# PWR_LTM4644.net
KiCad netlist of a schematic drawn in Altium Designer
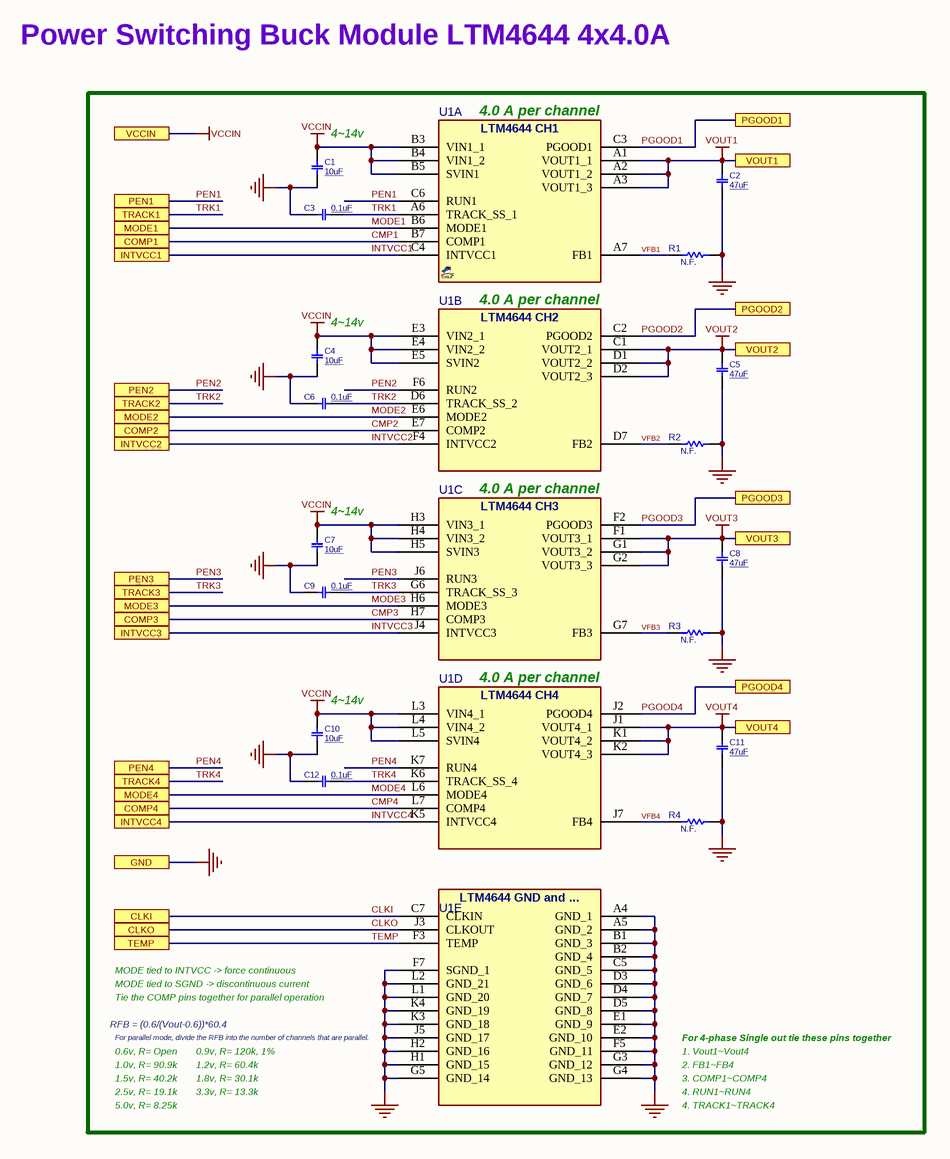
[diagram p0: PWR_LTM4644.SchDoc]

(export (version "E")
  (design (tool "Eeschema 10.0.6"))
  (components
    (comp (ref "C1")
      (value "10uF")
      (footprint "C0805")
      (description "CAP, MLCC")
      (libsource (lib "passive_smd") (part "CAP_SMD_MLCC"))
    )
    (comp (ref "C2")
      (value "47uF")
      (footprint "C0805")
      (description "CAP, MLCC")
      (libsource (lib "passive_smd") (part "CAP_SMD_MLCC"))
    )
    (comp (ref "C3")
      (value "0.1uF")
      (footprint "C0402")
      (description "CAP, MLCC")
      (libsource (lib "passive_smd") (part "CAP_SMD_MLCC"))
    )
    (comp (ref "C4")
      (value "10uF")
      (footprint "C0805")
      (description "CAP, MLCC")
      (libsource (lib "passive_smd") (part "CAP_SMD_MLCC"))
    )
    (comp (ref "C5")
      (value "47uF")
      (footprint "C0805")
      (description "CAP, MLCC")
      (libsource (lib "passive_smd") (part "CAP_SMD_MLCC"))
    )
    (comp (ref "C6")
      (value "0.1uF")
      (footprint "C0402")
      (description "CAP, MLCC")
      (libsource (lib "passive_smd") (part "CAP_SMD_MLCC"))
    )
    (comp (ref "C7")
      (value "10uF")
      (footprint "C0805")
      (description "CAP, MLCC")
      (libsource (lib "passive_smd") (part "CAP_SMD_MLCC"))
    )
    (comp (ref "C8")
      (value "47uF")
      (footprint "C0805")
      (description "CAP, MLCC")
      (libsource (lib "passive_smd") (part "CAP_SMD_MLCC"))
    )
    (comp (ref "C9")
      (value "0.1uF")
      (footprint "C0402")
      (description "CAP, MLCC")
      (libsource (lib "passive_smd") (part "CAP_SMD_MLCC"))
    )
    (comp (ref "C10")
      (value "10uF")
      (footprint "C0805")
      (description "CAP, MLCC")
      (libsource (lib "passive_smd") (part "CAP_SMD_MLCC"))
    )
    (comp (ref "C11")
      (value "47uF")
      (footprint "C0805")
      (description "CAP, MLCC")
      (libsource (lib "passive_smd") (part "CAP_SMD_MLCC"))
    )
    (comp (ref "C12")
      (value "0.1uF")
      (footprint "C0402")
      (description "CAP, MLCC")
      (libsource (lib "passive_smd") (part "CAP_SMD_MLCC"))
    )
    (comp (ref "R1")
      (value "N.F.")
      (footprint "R0402")
      (description "RESISTOR, SMD")
      (libsource (lib "passive_smd") (part "RES_SMD"))
    )
    (comp (ref "R2")
      (value "N.F.")
      (footprint "R0402")
      (description "RESISTOR, SMD")
      (libsource (lib "passive_smd") (part "RES_SMD"))
    )
    (comp (ref "R3")
      (value "N.F.")
      (footprint "R0402")
      (description "RESISTOR, SMD")
      (libsource (lib "passive_smd") (part "RES_SMD"))
    )
    (comp (ref "R4")
      (value "N.F.")
      (footprint "R0402")
      (description "RESISTOR, SMD")
      (libsource (lib "passive_smd") (part "RES_SMD"))
    )
    (comp (ref "U1")
      (value "LTM4644")
      (footprint "BGA127_77_1509")
      (description "DC2DC Switching MODULE, QUAD, 4A")
      (fields (field (name "MANF") "ANALOG DEVICE") (field (name "MANF_P#") "LTM4644EY, LTM4644IY"))
      (libsource (lib "pwr_switching_module") (part "LTM4644_BGA77"))
    )
  )
  (nets
    (net (code "1") (name "/CLKI") (class "Default")
      (node (ref "U1") (pin "C7") (pinfunction "CLKIN_C7") (pintype "passive"))
    )
    (net (code "2") (name "/CLKO") (class "Default")
      (node (ref "U1") (pin "J3") (pinfunction "CLKOUT_J3") (pintype "passive"))
    )
    (net (code "3") (name "/CMP1") (class "Default")
      (node (ref "U1") (pin "B7") (pinfunction "COMP1_B7") (pintype "passive"))
    )
    (net (code "4") (name "/CMP2") (class "Default")
      (node (ref "U1") (pin "E7") (pinfunction "COMP2_E7") (pintype "passive"))
    )
    (net (code "5") (name "/CMP3") (class "Default")
      (node (ref "U1") (pin "H7") (pinfunction "COMP3_H7") (pintype "passive"))
    )
    (net (code "6") (name "/CMP4") (class "Default")
      (node (ref "U1") (pin "L7") (pinfunction "COMP4_L7") (pintype "passive"))
    )
    (net (code "7") (name "/INTVCC1") (class "Default")
      (node (ref "U1") (pin "C4") (pinfunction "INTVCC1_C4") (pintype "passive"))
    )
    (net (code "8") (name "/INTVCC2") (class "Default")
      (node (ref "U1") (pin "F4") (pinfunction "INTVCC2_F4") (pintype "passive"))
    )
    (net (code "9") (name "/INTVCC3") (class "Default")
      (node (ref "U1") (pin "J4") (pinfunction "INTVCC3_J4") (pintype "passive"))
    )
    (net (code "10") (name "/INTVCC4") (class "Default")
      (node (ref "U1") (pin "K5") (pinfunction "INTVCC4_K5") (pintype "passive"))
    )
    (net (code "11") (name "/MODE1") (class "Default")
      (node (ref "U1") (pin "B6") (pinfunction "MODE1_B6") (pintype "passive"))
    )
    (net (code "12") (name "/MODE2") (class "Default")
      (node (ref "U1") (pin "E6") (pinfunction "MODE2_E6") (pintype "passive"))
    )
    (net (code "13") (name "/MODE3") (class "Default")
      (node (ref "U1") (pin "H6") (pinfunction "MODE3_H6") (pintype "passive"))
    )
    (net (code "14") (name "/MODE4") (class "Default")
      (node (ref "U1") (pin "L6") (pinfunction "MODE4_L6") (pintype "passive"))
    )
    (net (code "15") (name "/PEN1") (class "Default")
      (node (ref "U1") (pin "C6") (pinfunction "RUN1_C6") (pintype "passive"))
    )
    (net (code "16") (name "/PEN2") (class "Default")
      (node (ref "U1") (pin "F6") (pinfunction "RUN2_F6") (pintype "passive"))
    )
    (net (code "17") (name "/PEN3") (class "Default")
      (node (ref "U1") (pin "J6") (pinfunction "RUN3_J6") (pintype "passive"))
    )
    (net (code "18") (name "/PEN4") (class "Default")
      (node (ref "U1") (pin "K7") (pinfunction "RUN4_K7") (pintype "passive"))
    )
    (net (code "19") (name "/PGOOD1") (class "Default")
      (node (ref "U1") (pin "C3") (pinfunction "PGOOD1_C3") (pintype "passive"))
    )
    (net (code "20") (name "/PGOOD2") (class "Default")
      (node (ref "U1") (pin "C2") (pinfunction "PGOOD2_C2") (pintype "passive"))
    )
    (net (code "21") (name "/PGOOD3") (class "Default")
      (node (ref "U1") (pin "F2") (pinfunction "PGOOD3_F2") (pintype "passive"))
    )
    (net (code "22") (name "/PGOOD4") (class "Default")
      (node (ref "U1") (pin "J2") (pinfunction "PGOOD4_J2") (pintype "passive"))
    )
    (net (code "23") (name "/TEMP") (class "Default")
      (node (ref "U1") (pin "F3") (pinfunction "TEMP_F3") (pintype "passive"))
    )
    (net (code "24") (name "/TRK1") (class "Default")
      (node (ref "C3") (pin "2") (pinfunction "2_2") (pintype "passive"))
      (node (ref "U1") (pin "A6") (pinfunction "TRACK_SS_1_A6") (pintype "passive"))
    )
    (net (code "25") (name "/TRK2") (class "Default")
      (node (ref "C6") (pin "2") (pinfunction "2_2") (pintype "passive"))
      (node (ref "U1") (pin "D6") (pinfunction "TRACK_SS_2_D6") (pintype "passive"))
    )
    (net (code "26") (name "/TRK3") (class "Default")
      (node (ref "C9") (pin "2") (pinfunction "2_2") (pintype "passive"))
      (node (ref "U1") (pin "G6") (pinfunction "TRACK_SS_3_G6") (pintype "passive"))
    )
    (net (code "27") (name "/TRK4") (class "Default")
      (node (ref "C12") (pin "2") (pinfunction "2_2") (pintype "passive"))
      (node (ref "U1") (pin "K6") (pinfunction "TRACK_SS_4_K6") (pintype "passive"))
    )
    (net (code "28") (name "/VFB1") (class "Default")
      (node (ref "R1") (pin "2") (pinfunction "2_2") (pintype "passive"))
      (node (ref "U1") (pin "A7") (pinfunction "FB1_A7") (pintype "passive"))
    )
    (net (code "29") (name "/VFB2") (class "Default")
      (node (ref "R2") (pin "2") (pinfunction "2_2") (pintype "passive"))
      (node (ref "U1") (pin "D7") (pinfunction "FB2_D7") (pintype "passive"))
    )
    (net (code "30") (name "/VFB3") (class "Default")
      (node (ref "R3") (pin "2") (pinfunction "2_2") (pintype "passive"))
      (node (ref "U1") (pin "G7") (pinfunction "FB3_G7") (pintype "passive"))
    )
    (net (code "31") (name "/VFB4") (class "Default")
      (node (ref "R4") (pin "2") (pinfunction "2_2") (pintype "passive"))
      (node (ref "U1") (pin "J7") (pinfunction "FB4_J7") (pintype "passive"))
    )
    (net (code "32") (name "GND") (class "Default")
      (node (ref "C1") (pin "2") (pinfunction "2_2") (pintype "passive"))
      (node (ref "C10") (pin "2") (pinfunction "2_2") (pintype "passive"))
      (node (ref "C11") (pin "2") (pinfunction "2_2") (pintype "passive"))
      (node (ref "C12") (pin "1") (pinfunction "1_1") (pintype "passive"))
      (node (ref "C2") (pin "2") (pinfunction "2_2") (pintype "passive"))
      (node (ref "C3") (pin "1") (pinfunction "1_1") (pintype "passive"))
      (node (ref "C4") (pin "2") (pinfunction "2_2") (pintype "passive"))
      (node (ref "C5") (pin "2") (pinfunction "2_2") (pintype "passive"))
      (node (ref "C6") (pin "1") (pinfunction "1_1") (pintype "passive"))
      (node (ref "C7") (pin "2") (pinfunction "2_2") (pintype "passive"))
      (node (ref "C8") (pin "2") (pinfunction "2_2") (pintype "passive"))
      (node (ref "C9") (pin "1") (pinfunction "1_1") (pintype "passive"))
      (node (ref "R1") (pin "1") (pinfunction "1_1") (pintype "passive"))
      (node (ref "R2") (pin "1") (pinfunction "1_1") (pintype "passive"))
      (node (ref "R3") (pin "1") (pinfunction "1_1") (pintype "passive"))
      (node (ref "R4") (pin "1") (pinfunction "1_1") (pintype "passive"))
      (node (ref "U1") (pin "A4") (pinfunction "GND_1_A4") (pintype "passive"))
      (node (ref "U1") (pin "A5") (pinfunction "GND_2_A5") (pintype "passive"))
      (node (ref "U1") (pin "B1") (pinfunction "GND_3_B1") (pintype "passive"))
      (node (ref "U1") (pin "B2") (pinfunction "GND_4_B2") (pintype "passive"))
      (node (ref "U1") (pin "C5") (pinfunction "GND_5_C5") (pintype "passive"))
      (node (ref "U1") (pin "D3") (pinfunction "GND_6_D3") (pintype "passive"))
      (node (ref "U1") (pin "D4") (pinfunction "GND_7_D4") (pintype "passive"))
      (node (ref "U1") (pin "D5") (pinfunction "GND_8_D5") (pintype "passive"))
      (node (ref "U1") (pin "E1") (pinfunction "GND_9_E1") (pintype "passive"))
      (node (ref "U1") (pin "E2") (pinfunction "GND_10_E2") (pintype "passive"))
      (node (ref "U1") (pin "F5") (pinfunction "GND_11_F5") (pintype "passive"))
      (node (ref "U1") (pin "F7") (pinfunction "SGND_1_F7") (pintype "passive"))
      (node (ref "U1") (pin "G3") (pinfunction "GND_12_G3") (pintype "passive"))
      (node (ref "U1") (pin "G4") (pinfunction "GND_13_G4") (pintype "passive"))
      (node (ref "U1") (pin "G5") (pinfunction "GND_14_G5") (pintype "passive"))
      (node (ref "U1") (pin "H1") (pinfunction "GND_15_H1") (pintype "passive"))
      (node (ref "U1") (pin "H2") (pinfunction "GND_16_H2") (pintype "passive"))
      (node (ref "U1") (pin "J5") (pinfunction "GND_17_J5") (pintype "passive"))
      (node (ref "U1") (pin "K3") (pinfunction "GND_18_K3") (pintype "passive"))
      (node (ref "U1") (pin "K4") (pinfunction "GND_19_K4") (pintype "passive"))
      (node (ref "U1") (pin "L1") (pinfunction "GND_20_L1") (pintype "passive"))
      (node (ref "U1") (pin "L2") (pinfunction "GND_21_L2") (pintype "passive"))
    )
    (net (code "33") (name "VCCIN") (class "Default")
      (node (ref "C1") (pin "1") (pinfunction "1_1") (pintype "passive"))
      (node (ref "C10") (pin "1") (pinfunction "1_1") (pintype "passive"))
      (node (ref "C4") (pin "1") (pinfunction "1_1") (pintype "passive"))
      (node (ref "C7") (pin "1") (pinfunction "1_1") (pintype "passive"))
      (node (ref "U1") (pin "B3") (pinfunction "VIN1_1_B3") (pintype "passive"))
      (node (ref "U1") (pin "B4") (pinfunction "VIN1_2_B4") (pintype "passive"))
      (node (ref "U1") (pin "B5") (pinfunction "SVIN1_B5") (pintype "passive"))
      (node (ref "U1") (pin "E3") (pinfunction "VIN2_1_E3") (pintype "passive"))
      (node (ref "U1") (pin "E4") (pinfunction "VIN2_2_E4") (pintype "passive"))
      (node (ref "U1") (pin "E5") (pinfunction "SVIN2_E5") (pintype "passive"))
      (node (ref "U1") (pin "H3") (pinfunction "VIN3_1_H3") (pintype "passive"))
      (node (ref "U1") (pin "H4") (pinfunction "VIN3_2_H4") (pintype "passive"))
      (node (ref "U1") (pin "H5") (pinfunction "SVIN3_H5") (pintype "passive"))
      (node (ref "U1") (pin "L3") (pinfunction "VIN4_1_L3") (pintype "passive"))
      (node (ref "U1") (pin "L4") (pinfunction "VIN4_2_L4") (pintype "passive"))
      (node (ref "U1") (pin "L5") (pinfunction "SVIN4_L5") (pintype "passive"))
    )
    (net (code "34") (name "VOUT1") (class "Default")
      (node (ref "C2") (pin "1") (pinfunction "1_1") (pintype "passive"))
      (node (ref "U1") (pin "A1") (pinfunction "VOUT1_1_A1") (pintype "passive"))
      (node (ref "U1") (pin "A2") (pinfunction "VOUT1_2_A2") (pintype "passive"))
      (node (ref "U1") (pin "A3") (pinfunction "VOUT1_3_A3") (pintype "passive"))
    )
    (net (code "35") (name "VOUT2") (class "Default")
      (node (ref "C5") (pin "1") (pinfunction "1_1") (pintype "passive"))
      (node (ref "U1") (pin "C1") (pinfunction "VOUT2_1_C1") (pintype "passive"))
      (node (ref "U1") (pin "D1") (pinfunction "VOUT2_2_D1") (pintype "passive"))
      (node (ref "U1") (pin "D2") (pinfunction "VOUT2_3_D2") (pintype "passive"))
    )
    (net (code "36") (name "VOUT3") (class "Default")
      (node (ref "C8") (pin "1") (pinfunction "1_1") (pintype "passive"))
      (node (ref "U1") (pin "F1") (pinfunction "VOUT3_1_F1") (pintype "passive"))
      (node (ref "U1") (pin "G1") (pinfunction "VOUT3_2_G1") (pintype "passive"))
      (node (ref "U1") (pin "G2") (pinfunction "VOUT3_3_G2") (pintype "passive"))
    )
    (net (code "37") (name "VOUT4") (class "Default")
      (node (ref "C11") (pin "1") (pinfunction "1_1") (pintype "passive"))
      (node (ref "U1") (pin "J1") (pinfunction "VOUT4_1_J1") (pintype "passive"))
      (node (ref "U1") (pin "K1") (pinfunction "VOUT4_2_K1") (pintype "passive"))
      (node (ref "U1") (pin "K2") (pinfunction "VOUT4_3_K2") (pintype "passive"))
    )
  )
)
